# WiFiChessSch.net
KiCad netlist of a schematic drawn in Altium Designer
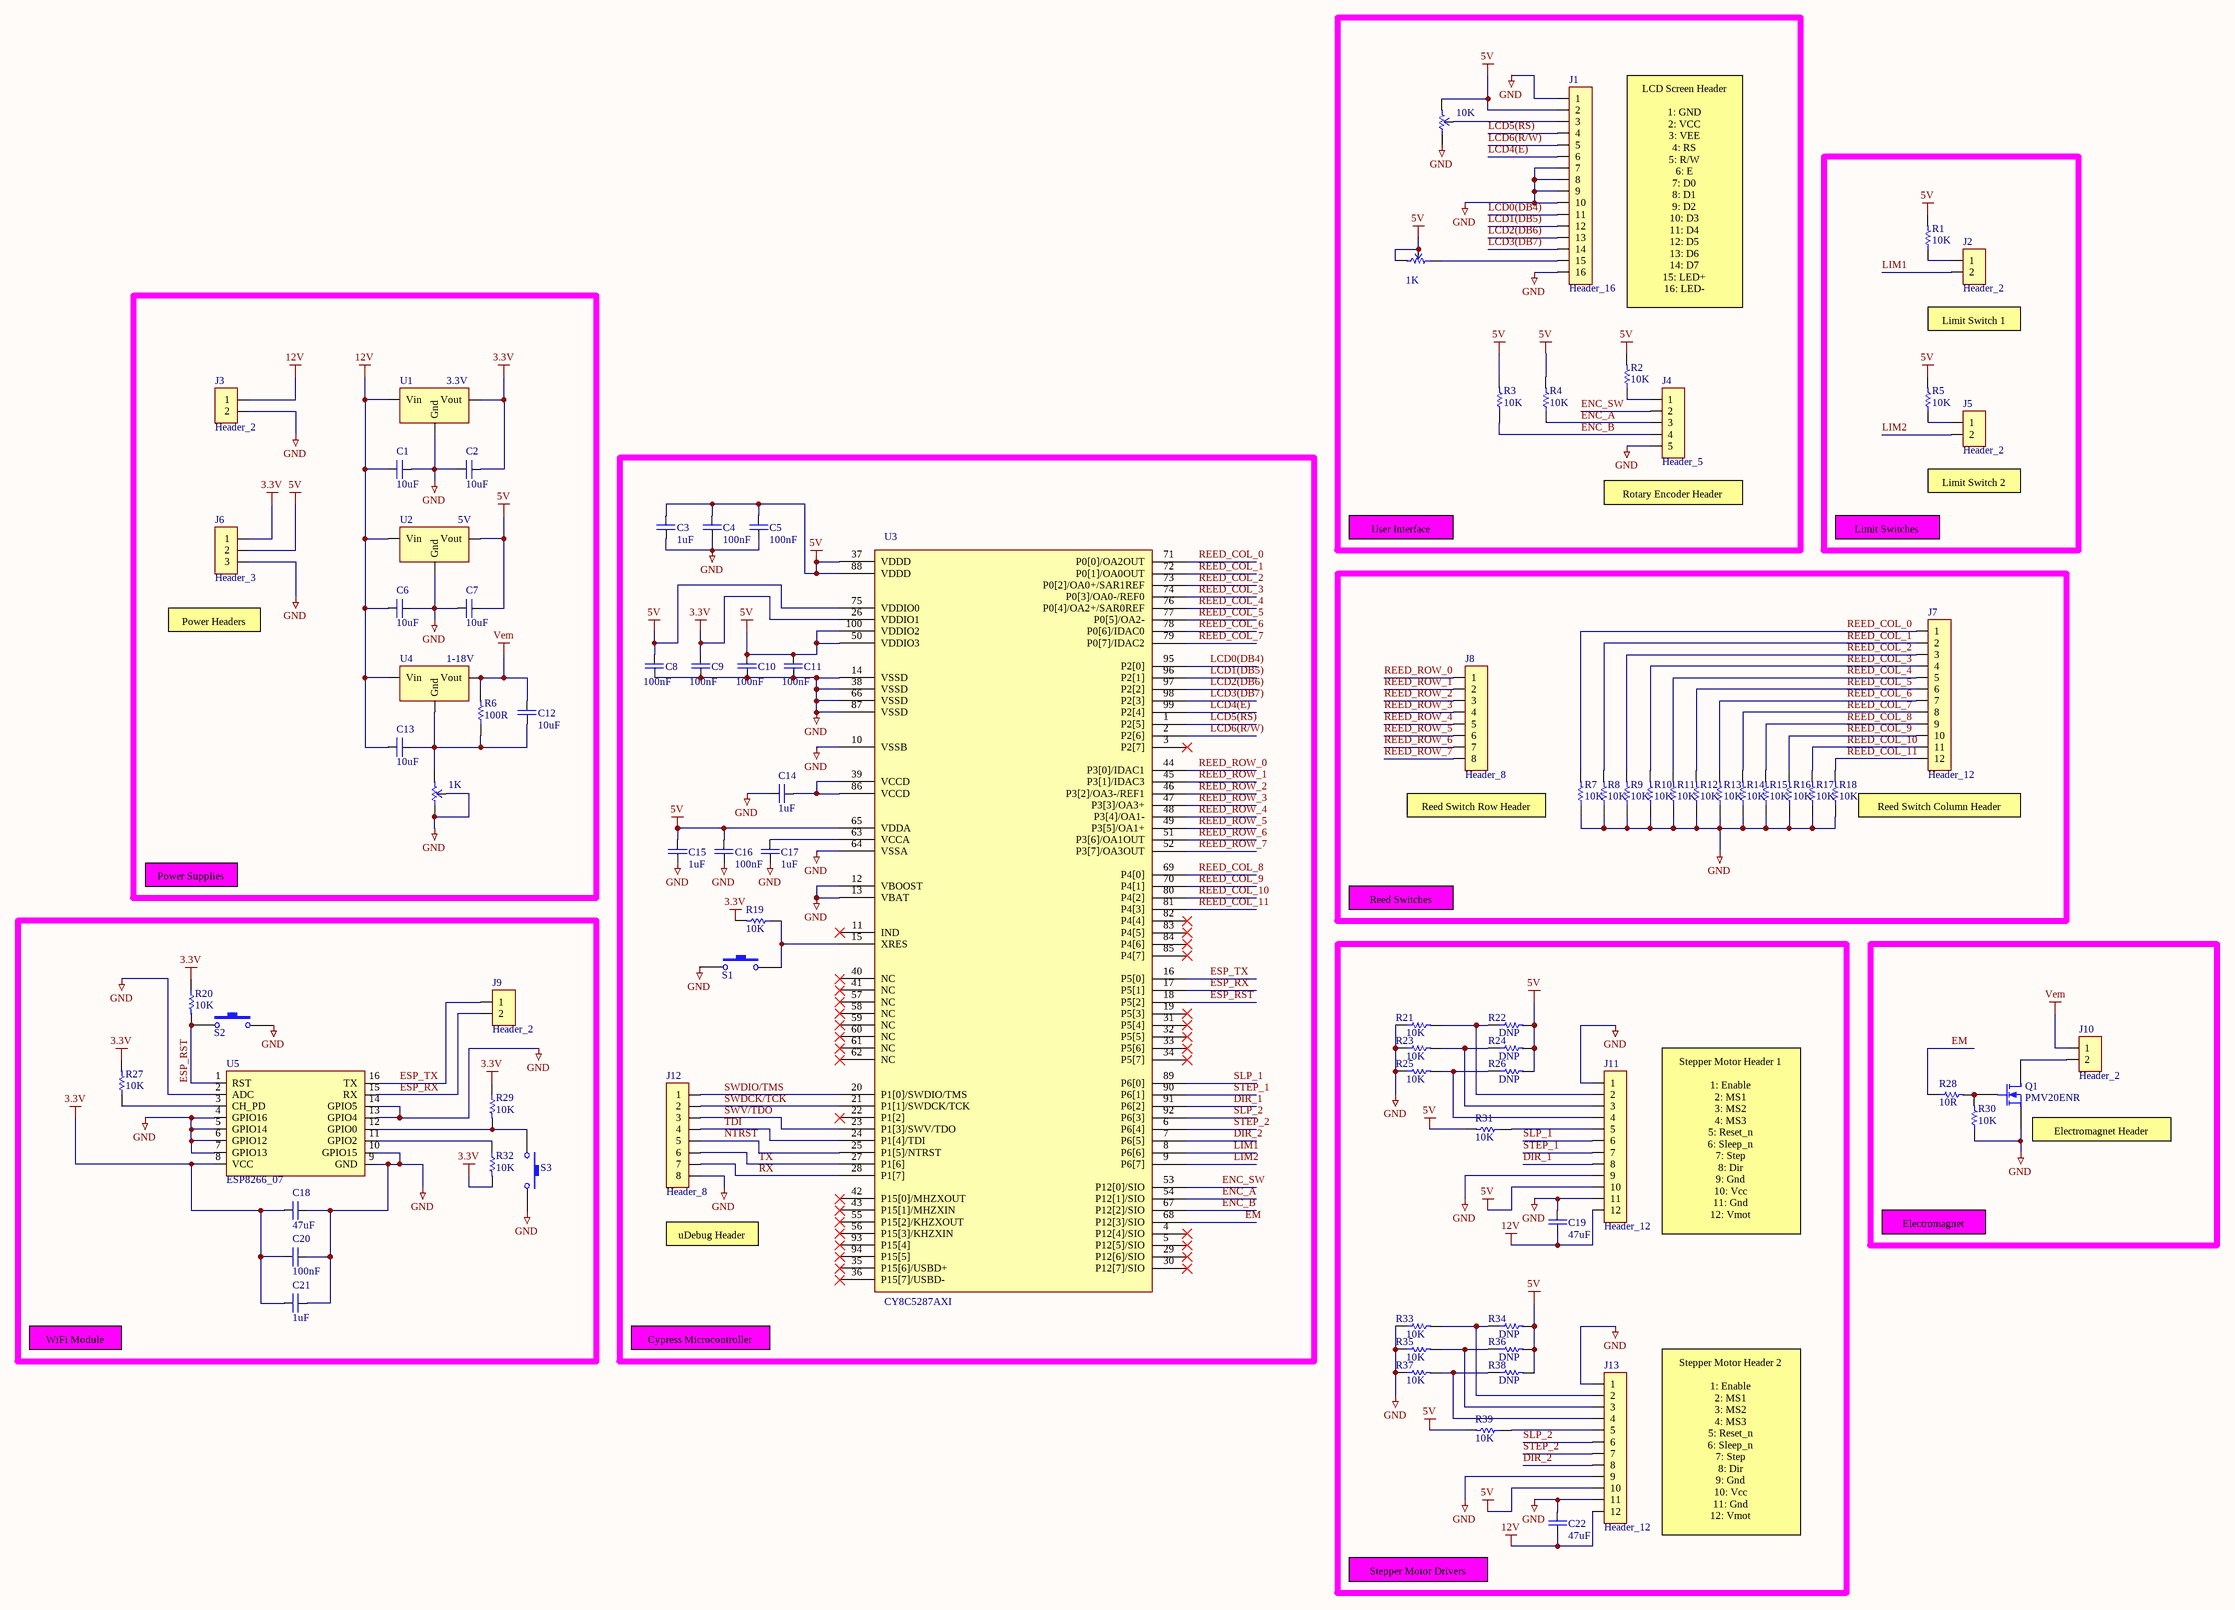
[diagram p0: WiFiChessSch.SchDoc]

(export (version "E")
  (design (tool "Eeschema 10.0.6"))
  (components
    (comp (ref "C1")
      (value "10uF")
      (footprint "CAP0603")
      (libsource (lib "Capacitor_0603") (part "Cap_10uF_0603"))
    )
    (comp (ref "C2")
      (value "10uF")
      (footprint "CAP0603")
      (libsource (lib "Capacitor_0603") (part "Cap_10uF_0603"))
    )
    (comp (ref "C3")
      (value "1uF")
      (footprint "CAP0603")
      (libsource (lib "Capacitor_0603") (part "Cap_1uF_0603"))
    )
    (comp (ref "C4")
      (value "100nF")
      (footprint "CAP0603")
      (libsource (lib "Capacitor_0603") (part "Cap_100nF_0603"))
    )
    (comp (ref "C5")
      (value "100nF")
      (footprint "CAP0603")
      (libsource (lib "Capacitor_0603") (part "Cap_100nF_0603"))
    )
    (comp (ref "C6")
      (value "10uF")
      (footprint "CAP0603")
      (libsource (lib "Capacitor_0603") (part "Cap_10uF_0603"))
    )
    (comp (ref "C7")
      (value "10uF")
      (footprint "CAP0603")
      (libsource (lib "Capacitor_0603") (part "Cap_10uF_0603"))
    )
    (comp (ref "C8")
      (value "100nF")
      (footprint "CAP0603")
      (libsource (lib "Capacitor_0603") (part "Cap_100nF_0603"))
    )
    (comp (ref "C9")
      (value "100nF")
      (footprint "CAP0603")
      (libsource (lib "Capacitor_0603") (part "Cap_100nF_0603"))
    )
    (comp (ref "C10")
      (value "100nF")
      (footprint "CAP0603")
      (libsource (lib "Capacitor_0603") (part "Cap_100nF_0603"))
    )
    (comp (ref "C11")
      (value "100nF")
      (footprint "CAP0603")
      (libsource (lib "Capacitor_0603") (part "Cap_100nF_0603"))
    )
    (comp (ref "C12")
      (value "10uF")
      (footprint "CAP0603")
      (libsource (lib "Capacitor_0603") (part "Cap_10uF_0603"))
    )
    (comp (ref "C13")
      (value "10uF")
      (footprint "CAP0603")
      (libsource (lib "Capacitor_0603") (part "Cap_10uF_0603"))
    )
    (comp (ref "C14")
      (value "1uF")
      (footprint "CAP0603")
      (libsource (lib "Capacitor_0603") (part "Cap_1uF_0603"))
    )
    (comp (ref "C15")
      (value "1uF")
      (footprint "CAP0603")
      (libsource (lib "Capacitor_0603") (part "Cap_1uF_0603"))
    )
    (comp (ref "C16")
      (value "100nF")
      (footprint "CAP0603")
      (libsource (lib "Capacitor_0603") (part "Cap_100nF_0603"))
    )
    (comp (ref "C17")
      (value "1uF")
      (footprint "CAP0603")
      (libsource (lib "Capacitor_0603") (part "Cap_1uF_0603"))
    )
    (comp (ref "C18")
      (value "47uF")
      (footprint "CAP_EL_8x5.9")
      (fields (field (name "MANUFACTURER") "Nichicon") (field (name "PART NUMBER") "UWT1E470MCL6GS"))
      (libsource (lib "Capacitor_Aluminum") (part "Cap_47uF_Alu"))
    )
    (comp (ref "C19")
      (value "47uF")
      (footprint "CAP_EL_8x5.9")
      (fields (field (name "MANUFACTURER") "Nichicon") (field (name "PART NUMBER") "UWT1E470MCL6GS"))
      (libsource (lib "Capacitor_Aluminum") (part "Cap_47uF_Alu"))
    )
    (comp (ref "C20")
      (value "100nF")
      (footprint "CAP0603")
      (libsource (lib "Capacitor_0603") (part "Cap_100nF_0603"))
    )
    (comp (ref "C21")
      (value "1uF")
      (footprint "CAP0603")
      (libsource (lib "Capacitor_0603") (part "Cap_1uF_0603"))
    )
    (comp (ref "C22")
      (value "47uF")
      (footprint "CAP_EL_8x5.9")
      (fields (field (name "MANUFACTURER") "Nichicon") (field (name "PART NUMBER") "UWT1E470MCL6GS"))
      (libsource (lib "Capacitor_Aluminum") (part "Cap_47uF_Alu"))
    )
    (comp (ref "J1")
      (value "Header_16")
      (footprint "16 Pin Header 2.54mm")
      (description "16 pin header")
      (libsource (lib "Connectors") (part "Header_16"))
    )
    (comp (ref "J2")
      (value "Header_2")
      (footprint "2 Pin Header 2.54mm")
      (description "2 Pin Header")
      (libsource (lib "Connectors") (part "Header_2"))
    )
    (comp (ref "J3")
      (value "Header_2")
      (footprint "2 Pin Header 2.54mm")
      (description "2 Pin Header")
      (libsource (lib "") (part "Header_2_1"))
    )
    (comp (ref "J4")
      (value "Header_5")
      (footprint "5 Pin Header 2.54mm")
      (description "5 Pin Header")
      (libsource (lib "Connectors") (part "Header_5"))
    )
    (comp (ref "J5")
      (value "Header_2")
      (footprint "2 Pin Header 2.54mm")
      (description "2 Pin Header")
      (libsource (lib "Connectors") (part "Header_2"))
    )
    (comp (ref "J6")
      (value "Header_3")
      (footprint "3 Pin Header 2.54mm")
      (description "3 Pin Header")
      (libsource (lib "Connectors") (part "Header_3"))
    )
    (comp (ref "J7")
      (value "Header_12")
      (footprint "12 Pin Header 2.54mm")
      (description "12 Pin Header")
      (libsource (lib "Connectors") (part "Header_12"))
    )
    (comp (ref "J8")
      (value "Header_8")
      (footprint "8 Pin Header 2.54mm")
      (description "8 Pin Header")
      (libsource (lib "") (part "Header_8_1"))
    )
    (comp (ref "J9")
      (value "Header_2")
      (footprint "2 Pin Header 2.54mm")
      (description "2 Pin Header")
      (libsource (lib "Connectors") (part "Header_2"))
    )
    (comp (ref "J10")
      (value "Header_2")
      (footprint "2 Pin Header 2.54mm")
      (description "2 Pin Header")
      (libsource (lib "Connectors") (part "Header_2"))
    )
    (comp (ref "J11")
      (value "Header_12")
      (footprint "12 Pin Header 2.54mm")
      (description "12 Pin Header")
      (libsource (lib "Connectors") (part "Header_12"))
    )
    (comp (ref "J12")
      (value "Header_8")
      (footprint "8 Pin Header 2.54mm")
      (description "8 Pin Header")
      (libsource (lib "Connectors") (part "Header_8"))
    )
    (comp (ref "J13")
      (value "Header_12")
      (footprint "12 Pin Header 2.54mm")
      (description "12 Pin Header")
      (libsource (lib "Connectors") (part "Header_12"))
    )
    (comp (ref "Q1")
      (value "PMV20ENR")
      (footprint "SOT23")
      (description "Logic Level P-FET")
      (fields (field (name "MANUFACTURER") "NXP Semiconductor"))
      (libsource (lib "Transistors") (part "PMV20ENR"))
    )
    (comp (ref "R1")
      (value "10K")
      (footprint "RES0603")
      (description "Resistor")
      (fields (field (name "PART NUMBER") "RC0603JR-0710KL") (field (name "MANUFACTURER") "Yageo"))
      (libsource (lib "Resistor_0603") (part "Res_10K_0603"))
    )
    (comp (ref "R2")
      (value "10K")
      (footprint "RES0603")
      (description "Resistor")
      (fields (field (name "PART NUMBER") "RC0603JR-0710KL") (field (name "MANUFACTURER") "Yageo"))
      (libsource (lib "Resistor_0603") (part "Res_10K_0603"))
    )
    (comp (ref "R3")
      (value "10K")
      (footprint "RES0603")
      (description "Resistor")
      (fields (field (name "PART NUMBER") "RC0603JR-0710KL") (field (name "MANUFACTURER") "Yageo"))
      (libsource (lib "Resistor_0603") (part "Res_10K_0603"))
    )
    (comp (ref "R4")
      (value "10K")
      (footprint "RES0603")
      (description "Resistor")
      (fields (field (name "PART NUMBER") "RC0603JR-0710KL") (field (name "MANUFACTURER") "Yageo"))
      (libsource (lib "Resistor_0603") (part "Res_10K_0603"))
    )
    (comp (ref "R5")
      (value "10K")
      (footprint "RES0603")
      (description "Resistor")
      (fields (field (name "PART NUMBER") "RC0603JR-0710KL") (field (name "MANUFACTURER") "Yageo"))
      (libsource (lib "Resistor_0603") (part "Res_10K_0603"))
    )
    (comp (ref "R6")
      (value "100R")
      (footprint "RES0603")
      (description "Resistor")
      (fields (field (name "TOLERANCE") "5%"))
      (libsource (lib "Resistor_0603") (part "Res_100R_0603_1"))
    )
    (comp (ref "R7")
      (value "10K")
      (footprint "RES0603")
      (description "Resistor")
      (fields (field (name "PART NUMBER") "RC0603JR-0710KL") (field (name "MANUFACTURER") "Yageo"))
      (libsource (lib "Resistor_0603") (part "Res_10K_0603"))
    )
    (comp (ref "R8")
      (value "10K")
      (footprint "RES0603")
      (description "Resistor")
      (fields (field (name "PART NUMBER") "RC0603JR-0710KL") (field (name "MANUFACTURER") "Yageo"))
      (libsource (lib "Resistor_0603") (part "Res_10K_0603"))
    )
    (comp (ref "R9")
      (value "10K")
      (footprint "RES0603")
      (description "Resistor")
      (fields (field (name "PART NUMBER") "RC0603JR-0710KL") (field (name "MANUFACTURER") "Yageo"))
      (libsource (lib "Resistor_0603") (part "Res_10K_0603"))
    )
    (comp (ref "R10")
      (value "10K")
      (footprint "RES0603")
      (description "Resistor")
      (fields (field (name "PART NUMBER") "RC0603JR-0710KL") (field (name "MANUFACTURER") "Yageo"))
      (libsource (lib "Resistor_0603") (part "Res_10K_0603"))
    )
    (comp (ref "R11")
      (value "10K")
      (footprint "RES0603")
      (description "Resistor")
      (fields (field (name "PART NUMBER") "RC0603JR-0710KL") (field (name "MANUFACTURER") "Yageo"))
      (libsource (lib "Resistor_0603") (part "Res_10K_0603"))
    )
    (comp (ref "R12")
      (value "10K")
      (footprint "RES0603")
      (description "Resistor")
      (fields (field (name "PART NUMBER") "RC0603JR-0710KL") (field (name "MANUFACTURER") "Yageo"))
      (libsource (lib "Resistor_0603") (part "Res_10K_0603"))
    )
    (comp (ref "R13")
      (value "10K")
      (footprint "RES0603")
      (description "Resistor")
      (fields (field (name "PART NUMBER") "RC0603JR-0710KL") (field (name "MANUFACTURER") "Yageo"))
      (libsource (lib "Resistor_0603") (part "Res_10K_0603"))
    )
    (comp (ref "R14")
      (value "10K")
      (footprint "RES0603")
      (description "Resistor")
      (fields (field (name "PART NUMBER") "RC0603JR-0710KL") (field (name "MANUFACTURER") "Yageo"))
      (libsource (lib "Resistor_0603") (part "Res_10K_0603"))
    )
    (comp (ref "R15")
      (value "10K")
      (footprint "RES0603")
      (description "Resistor")
      (fields (field (name "PART NUMBER") "RC0603JR-0710KL") (field (name "MANUFACTURER") "Yageo"))
      (libsource (lib "Resistor_0603") (part "Res_10K_0603"))
    )
    (comp (ref "R16")
      (value "10K")
      (footprint "RES0603")
      (description "Resistor")
      (fields (field (name "PART NUMBER") "RC0603JR-0710KL") (field (name "MANUFACTURER") "Yageo"))
      (libsource (lib "Resistor_0603") (part "Res_10K_0603"))
    )
    (comp (ref "R17")
      (value "10K")
      (footprint "RES0603")
      (description "Resistor")
      (fields (field (name "PART NUMBER") "RC0603JR-0710KL") (field (name "MANUFACTURER") "Yageo"))
      (libsource (lib "Resistor_0603") (part "Res_10K_0603"))
    )
    (comp (ref "R18")
      (value "10K")
      (footprint "RES0603")
      (description "Resistor")
      (fields (field (name "PART NUMBER") "RC0603JR-0710KL") (field (name "MANUFACTURER") "Yageo"))
      (libsource (lib "Resistor_0603") (part "Res_10K_0603"))
    )
    (comp (ref "R19")
      (value "10K")
      (footprint "RES0603")
      (description "Resistor")
      (fields (field (name "PART NUMBER") "RC0603JR-0710KL") (field (name "MANUFACTURER") "Yageo"))
      (libsource (lib "Resistor_0603") (part "Res_10K_0603"))
    )
    (comp (ref "R20")
      (value "10K")
      (footprint "RES0603")
      (description "Resistor")
      (fields (field (name "PART NUMBER") "RC0603JR-0710KL") (field (name "MANUFACTURER") "Yageo"))
      (libsource (lib "Resistor_0603") (part "Res_10K_0603"))
    )
    (comp (ref "R21")
      (value "10K")
      (footprint "RES0603")
      (description "Resistor")
      (fields (field (name "PART NUMBER") "RC0603JR-0710KL") (field (name "MANUFACTURER") "Yageo"))
      (libsource (lib "Resistor_0603") (part "Res_10K_0603"))
    )
    (comp (ref "R22")
      (value "DNP")
      (footprint "RES0603")
      (description "Resistor")
      (fields (field (name "TOLERANCE") "5%"))
      (libsource (lib "Resistor_0603") (part "Res_0603_DNP"))
    )
    (comp (ref "R23")
      (value "10K")
      (footprint "RES0603")
      (description "Resistor")
      (fields (field (name "PART NUMBER") "RC0603JR-0710KL") (field (name "MANUFACTURER") "Yageo"))
      (libsource (lib "Resistor_0603") (part "Res_10K_0603"))
    )
    (comp (ref "R24")
      (value "DNP")
      (footprint "RES0603")
      (description "Resistor")
      (fields (field (name "TOLERANCE") "5%"))
      (libsource (lib "Resistor_0603") (part "Res_0603_DNP"))
    )
    (comp (ref "R25")
      (value "10K")
      (footprint "RES0603")
      (description "Resistor")
      (fields (field (name "PART NUMBER") "RC0603JR-0710KL") (field (name "MANUFACTURER") "Yageo"))
      (libsource (lib "Resistor_0603") (part "Res_10K_0603"))
    )
    (comp (ref "R26")
      (value "DNP")
      (footprint "RES0603")
      (description "Resistor")
      (fields (field (name "TOLERANCE") "5%"))
      (libsource (lib "Resistor_0603") (part "Res_0603_DNP"))
    )
    (comp (ref "R27")
      (value "10K")
      (footprint "RES0603")
      (description "Resistor")
      (fields (field (name "PART NUMBER") "RC0603JR-0710KL") (field (name "MANUFACTURER") "Yageo"))
      (libsource (lib "Resistor_0603") (part "Res_10K_0603"))
    )
    (comp (ref "R28")
      (value "10R")
      (footprint "RES0603")
      (description "Resistor")
      (fields (field (name "TOLERANCE") "5%"))
      (libsource (lib "Resistor_0603") (part "Res_10R_0603"))
    )
    (comp (ref "R29")
      (value "10K")
      (footprint "RES0603")
      (description "Resistor")
      (fields (field (name "PART NUMBER") "RC0603JR-0710KL") (field (name "MANUFACTURER") "Yageo"))
      (libsource (lib "Resistor_0603") (part "Res_10K_0603"))
    )
    (comp (ref "R30")
      (value "10K")
      (footprint "RES0603")
      (description "Resistor")
      (fields (field (name "PART NUMBER") "RC0603JR-0710KL") (field (name "MANUFACTURER") "Yageo"))
      (libsource (lib "Resistor_0603") (part "Res_10K_0603"))
    )
    (comp (ref "R31")
      (value "10K")
      (footprint "RES0603")
      (description "Resistor")
      (fields (field (name "PART NUMBER") "RC0603JR-0710KL") (field (name "MANUFACTURER") "Yageo"))
      (libsource (lib "Resistor_0603") (part "Res_10K_0603"))
    )
    (comp (ref "R32")
      (value "10K")
      (footprint "RES0603")
      (description "Resistor")
      (fields (field (name "PART NUMBER") "RC0603JR-0710KL") (field (name "MANUFACTURER") "Yageo"))
      (libsource (lib "Resistor_0603") (part "Res_10K_0603"))
    )
    (comp (ref "R33")
      (value "10K")
      (footprint "RES0603")
      (description "Resistor")
      (fields (field (name "PART NUMBER") "RC0603JR-0710KL") (field (name "MANUFACTURER") "Yageo"))
      (libsource (lib "Resistor_0603") (part "Res_10K_0603"))
    )
    (comp (ref "R34")
      (value "DNP")
      (footprint "RES0603")
      (description "Resistor")
      (fields (field (name "TOLERANCE") "5%"))
      (libsource (lib "Resistor_0603") (part "Res_0603_DNP"))
    )
    (comp (ref "R35")
      (value "10K")
      (footprint "RES0603")
      (description "Resistor")
      (fields (field (name "PART NUMBER") "RC0603JR-0710KL") (field (name "MANUFACTURER") "Yageo"))
      (libsource (lib "Resistor_0603") (part "Res_10K_0603"))
    )
    (comp (ref "R36")
      (value "DNP")
      (footprint "RES0603")
      (description "Resistor")
      (fields (field (name "TOLERANCE") "5%"))
      (libsource (lib "Resistor_0603") (part "Res_0603_DNP"))
    )
    (comp (ref "R37")
      (value "10K")
      (footprint "RES0603")
      (description "Resistor")
      (fields (field (name "PART NUMBER") "RC0603JR-0710KL") (field (name "MANUFACTURER") "Yageo"))
      (libsource (lib "Resistor_0603") (part "Res_10K_0603"))
    )
    (comp (ref "R38")
      (value "DNP")
      (footprint "RES0603")
      (description "Resistor")
      (fields (field (name "TOLERANCE") "5%"))
      (libsource (lib "Resistor_0603") (part "Res_0603_DNP"))
    )
    (comp (ref "R39")
      (value "10K")
      (footprint "RES0603")
      (description "Resistor")
      (fields (field (name "PART NUMBER") "RC0603JR-0710KL") (field (name "MANUFACTURER") "Yageo"))
      (libsource (lib "Resistor_0603") (part "Res_10K_0603"))
    )
    (comp (ref "S1")
      (value "NO-Tactile Switch")
      (footprint "FSM2JSMAATR")
      (description "Switch")
      (fields
        (field (name "PART NUMBER") "PTS645SK50SMTR92 LFS")
        (field (name "MANUFACTURER") "C&K Components")
      )
      (libsource (lib "Switches") (part "NO-Tactile Switch"))
    )
    (comp (ref "S2")
      (value "NO-Tactile Switch")
      (footprint "FSM2JSMAATR")
      (description "Switch")
      (fields
        (field (name "PART NUMBER") "PTS645SK50SMTR92 LFS")
        (field (name "MANUFACTURER") "C&K Components")
      )
      (libsource (lib "Switches") (part "NO-Tactile Switch"))
    )
    (comp (ref "S3")
      (value "NO-Tactile Switch")
      (footprint "FSM2JSMAATR")
      (description "Switch")
      (fields
        (field (name "PART NUMBER") "PTS645SK50SMTR92 LFS")
        (field (name "MANUFACTURER") "C&K Components")
      )
      (libsource (lib "Switches") (part "NO-Tactile Switch"))
    )
    (comp (ref "U1")
      (value "3.3V")
      (footprint "SOT223")
      (description "3.3V_800mA_Linear")
      (fields (field (name "PART NUMBER") "NCP1117ST33T3G") (field (name "MANUFACTURER") "ON Semiconductor"))
      (libsource (lib "Voltage_Regulators") (part "NCP1117ST33T3G"))
    )
    (comp (ref "U2")
      (value "5V")
      (footprint "SOT223")
      (description "5V_1A_Linear")
      (fields (field (name "PART NUMBER") "NCV1117ST50T3G") (field (name "MANUFACTURER") "ON Semiconductor"))
      (libsource (lib "Voltage_Regulators") (part "NCV1117ST50T3G"))
    )
    (comp (ref "U3")
      (value "CY8C5287AXI")
      (footprint "TQPF-100")
      (description "Cypress CY8C52 PSoC 5")
      (fields
        (field (name "PART NUMBER") "CY8C5287AXI-LP095")
        (field (name "MANUFACTURER") "Cypress Semiconductor")
      )
      (libsource (lib "Microcontrollers") (part "CY8C5287AXI"))
    )
    (comp (ref "U4")
      (value "1-18V")
      (footprint "SOT223")
      (description "Adj_1A_Linear")
      (fields (field (name "PART NUMBER") "NCV1117STAT3G") (field (name "MANUFACTURER") "ON Semiconductor"))
      (libsource (lib "Voltage_Regulators") (part "NCV1117STAT3G"))
    )
    (comp (ref "U5")
      (value "ESP8266_07")
      (footprint "ESP-07")
      (description "ESP-07 WiFi Module")
      (libsource (lib "Modules") (part "ESP8266_07"))
    )
    (comp (ref "VR1")
      (value "10K")
      (footprint "RESPVZ3A")
      (fields
        (field (name "PART NUMBER") "PVZ3A103C01R00")
        (field (name "MANUFACTURER") "Murata Electronics")
      )
      (libsource (lib "Potentiometer") (part "PVZ3A_10K_Trimmer_Pot"))
    )
    (comp (ref "VR2")
      (value "1K")
      (footprint "RESPVZ3A")
      (fields
        (field (name "PART NUMBER") "PVZ3A102C01R00")
        (field (name "MANUFACTURER") "Murata Electronics")
      )
      (libsource (lib "Potentiometer") (part "PVZ3A_1K_Trimmer_Pot"))
    )
    (comp (ref "VR3")
      (value "1K")
      (footprint "RESPVZ3A")
      (fields
        (field (name "PART NUMBER") "PVZ3A102C01R00")
        (field (name "MANUFACTURER") "Murata Electronics")
      )
      (libsource (lib "Potentiometer") (part "PVZ3A_1K_Trimmer_Pot"))
    )
  )
  (nets
    (net (code "1") (name "/DIR_1") (class "Default")
      (node (ref "J11") (pin "8") (pinfunction "8_8") (pintype "passive"))
      (node (ref "U3") (pin "91") (pinfunction "P6[2]_91") (pintype "passive"))
    )
    (net (code "2") (name "/DIR_2") (class "Default")
      (node (ref "J13") (pin "8") (pinfunction "8_8") (pintype "passive"))
      (node (ref "U3") (pin "7") (pinfunction "P6[5]_7") (pintype "passive"))
    )
    (net (code "3") (name "/EM") (class "Default")
      (node (ref "R28") (pin "1") (pinfunction "1_1") (pintype "passive"))
      (node (ref "U3") (pin "68") (pinfunction "P12[3]/SIO_68") (pintype "passive"))
    )
    (net (code "4") (name "/ENC_A") (class "Default")
      (node (ref "J4") (pin "3") (pinfunction "3_3") (pintype "passive"))
      (node (ref "R4") (pin "1") (pinfunction "1_1") (pintype "passive"))
      (node (ref "U3") (pin "54") (pinfunction "P12[1]/SIO_54") (pintype "passive"))
    )
    (net (code "5") (name "/ENC_B") (class "Default")
      (node (ref "J4") (pin "4") (pinfunction "4_4") (pintype "passive"))
      (node (ref "R3") (pin "1") (pinfunction "1_1") (pintype "passive"))
      (node (ref "U3") (pin "67") (pinfunction "P12[2]/SIO_67") (pintype "passive"))
    )
    (net (code "6") (name "/ENC_SW") (class "Default")
      (node (ref "J4") (pin "2") (pinfunction "2_2") (pintype "passive"))
      (node (ref "U3") (pin "53") (pinfunction "P12[0]/SIO_53") (pintype "passive"))
    )
    (net (code "7") (name "/ESP_RST") (class "Default")
      (node (ref "R20") (pin "2") (pinfunction "2_2") (pintype "passive"))
      (node (ref "S2") (pin "1") (pinfunction "1_1") (pintype "passive"))
      (node (ref "U3") (pin "18") (pinfunction "P5[2]_18") (pintype "passive"))
      (node (ref "U5") (pin "1") (pinfunction "RST_1") (pintype "passive"))
    )
    (net (code "8") (name "/ESP_RX") (class "Default")
      (node (ref "J9") (pin "2") (pinfunction "2_2") (pintype "passive"))
      (node (ref "U3") (pin "17") (pinfunction "P5[1]_17") (pintype "passive"))
      (node (ref "U5") (pin "15") (pinfunction "RX_15") (pintype "passive"))
    )
    (net (code "9") (name "/ESP_TX") (class "Default")
      (node (ref "J9") (pin "1") (pinfunction "1_1") (pintype "passive"))
      (node (ref "U3") (pin "16") (pinfunction "P5[0]_16") (pintype "passive"))
      (node (ref "U5") (pin "16") (pinfunction "TX_16") (pintype "passive"))
    )
    (net (code "10") (name "/LCD0(DB4)") (class "Default")
      (node (ref "J1") (pin "11") (pinfunction "11_11") (pintype "passive"))
      (node (ref "U3") (pin "95") (pinfunction "P2[0]_95") (pintype "passive"))
    )
    (net (code "11") (name "/LCD1(DB5)") (class "Default")
      (node (ref "J1") (pin "12") (pinfunction "12_12") (pintype "passive"))
      (node (ref "U3") (pin "96") (pinfunction "P2[1]_96") (pintype "passive"))
    )
    (net (code "12") (name "/LCD2(DB6)") (class "Default")
      (node (ref "J1") (pin "13") (pinfunction "13_13") (pintype "passive"))
      (node (ref "U3") (pin "97") (pinfunction "P2[2]_97") (pintype "passive"))
    )
    (net (code "13") (name "/LCD3(DB7)") (class "Default")
      (node (ref "J1") (pin "14") (pinfunction "14_14") (pintype "passive"))
      (node (ref "U3") (pin "98") (pinfunction "P2[3]_98") (pintype "passive"))
    )
    (net (code "14") (name "/LCD4(E)") (class "Default")
      (node (ref "J1") (pin "6") (pinfunction "6_6") (pintype "passive"))
      (node (ref "U3") (pin "99") (pinfunction "P2[4]_99") (pintype "passive"))
    )
    (net (code "15") (name "/LCD5(RS)") (class "Default")
      (node (ref "J1") (pin "4") (pinfunction "4_4") (pintype "passive"))
      (node (ref "U3") (pin "1") (pinfunction "P2[5]_1") (pintype "passive"))
    )
    (net (code "16") (name "/LCD6(R{slash}W)") (class "Default")
      (node (ref "J1") (pin "5") (pinfunction "5_5") (pintype "passive"))
      (node (ref "U3") (pin "2") (pinfunction "P2[6]_2") (pintype "passive"))
    )
    (net (code "17") (name "/LIM1") (class "Default")
      (node (ref "J2") (pin "2") (pinfunction "2_2") (pintype "passive"))
      (node (ref "U3") (pin "8") (pinfunction "P6[6]_8") (pintype "passive"))
    )
    (net (code "18") (name "/LIM2") (class "Default")
      (node (ref "J5") (pin "2") (pinfunction "2_2") (pintype "passive"))
      (node (ref "U3") (pin "9") (pinfunction "P6[7]_9") (pintype "passive"))
    )
    (net (code "19") (name "/NTRST") (class "Default")
      (node (ref "J12") (pin "5") (pinfunction "5_5") (pintype "passive"))
      (node (ref "U3") (pin "25") (pinfunction "P1[5]/NTRST_25") (pintype "passive"))
    )
    (net (code "20") (name "/REED_COL_0") (class "Default")
      (node (ref "J7") (pin "1") (pinfunction "1_1") (pintype "passive"))
      (node (ref "R7") (pin "2") (pinfunction "2_2") (pintype "passive"))
      (node (ref "U3") (pin "71") (pinfunction "P0[0]/OA2OUT_71") (pintype "passive"))
    )
    (net (code "21") (name "/REED_COL_1") (class "Default")
      (node (ref "J7") (pin "2") (pinfunction "2_2") (pintype "passive"))
      (node (ref "R8") (pin "2") (pinfunction "2_2") (pintype "passive"))
      (node (ref "U3") (pin "72") (pinfunction "P0[1]/OA0OUT_72") (pintype "passive"))
    )
    (net (code "22") (name "/REED_COL_2") (class "Default")
      (node (ref "J7") (pin "3") (pinfunction "3_3") (pintype "passive"))
      (node (ref "R9") (pin "2") (pinfunction "2_2") (pintype "passive"))
      (node (ref "U3") (pin "73") (pinfunction "P0[2]/OA0+/SAR1REF_73") (pintype "passive"))
    )
    (net (code "23") (name "/REED_COL_3") (class "Default")
      (node (ref "J7") (pin "4") (pinfunction "4_4") (pintype "passive"))
      (node (ref "R10") (pin "2") (pinfunction "2_2") (pintype "passive"))
      (node (ref "U3") (pin "74") (pinfunction "P0[3]/OA0-/REF0_74") (pintype "passive"))
    )
    (net (code "24") (name "/REED_COL_4") (class "Default")
      (node (ref "J7") (pin "5") (pinfunction "5_5") (pintype "passive"))
      (node (ref "R11") (pin "2") (pinfunction "2_2") (pintype "passive"))
      (node (ref "U3") (pin "76") (pinfunction "P0[4]/OA2+/SAR0REF_76") (pintype "passive"))
    )
    (net (code "25") (name "/REED_COL_5") (class "Default")
      (node (ref "J7") (pin "6") (pinfunction "6_6") (pintype "passive"))
      (node (ref "R12") (pin "2") (pinfunction "2_2") (pintype "passive"))
      (node (ref "U3") (pin "77") (pinfunction "P0[5]/OA2-_77") (pintype "passive"))
    )
    (net (code "26") (name "/REED_COL_6") (class "Default")
      (node (ref "J7") (pin "7") (pinfunction "7_7") (pintype "passive"))
      (node (ref "R13") (pin "2") (pinfunction "2_2") (pintype "passive"))
      (node (ref "U3") (pin "78") (pinfunction "P0[6]/IDAC0_78") (pintype "passive"))
    )
    (net (code "27") (name "/REED_COL_7") (class "Default")
      (node (ref "J7") (pin "8") (pinfunction "8_8") (pintype "passive"))
      (node (ref "R14") (pin "2") (pinfunction "2_2") (pintype "passive"))
      (node (ref "U3") (pin "79") (pinfunction "P0[7]/IDAC2_79") (pintype "passive"))
    )
    (net (code "28") (name "/REED_COL_8") (class "Default")
      (node (ref "J7") (pin "9") (pinfunction "9_9") (pintype "passive"))
      (node (ref "R15") (pin "2") (pinfunction "2_2") (pintype "passive"))
      (node (ref "U3") (pin "69") (pinfunction "P4[0]_69") (pintype "passive"))
    )
    (net (code "29") (name "/REED_COL_9") (class "Default")
      (node (ref "J7") (pin "10") (pinfunction "10_10") (pintype "passive"))
      (node (ref "R16") (pin "2") (pinfunction "2_2") (pintype "passive"))
      (node (ref "U3") (pin "70") (pinfunction "P4[1]_70") (pintype "passive"))
    )
    (net (code "30") (name "/REED_COL_10") (class "Default")
      (node (ref "J7") (pin "11") (pinfunction "11_11") (pintype "passive"))
      (node (ref "R17") (pin "2") (pinfunction "2_2") (pintype "passive"))
      (node (ref "U3") (pin "80") (pinfunction "P4[2]_80") (pintype "passive"))
    )
    (net (code "31") (name "/REED_COL_11") (class "Default")
      (node (ref "J7") (pin "12") (pinfunction "12_12") (pintype "passive"))
      (node (ref "R18") (pin "2") (pinfunction "2_2") (pintype "passive"))
      (node (ref "U3") (pin "81") (pinfunction "P4[3]_81") (pintype "passive"))
    )
    (net (code "32") (name "/REED_ROW_0") (class "Default")
      (node (ref "J8") (pin "1") (pinfunction "1_1") (pintype "passive"))
      (node (ref "U3") (pin "44") (pinfunction "P3[0]/IDAC1_44") (pintype "passive"))
    )
    (net (code "33") (name "/REED_ROW_1") (class "Default")
      (node (ref "J8") (pin "2") (pinfunction "2_2") (pintype "passive"))
      (node (ref "U3") (pin "45") (pinfunction "P3[1]/IDAC3_45") (pintype "passive"))
    )
    (net (code "34") (name "/REED_ROW_2") (class "Default")
      (node (ref "J8") (pin "3") (pinfunction "3_3") (pintype "passive"))
      (node (ref "U3") (pin "46") (pinfunction "P3[2]/OA3-/REF1_46") (pintype "passive"))
    )
    (net (code "35") (name "/REED_ROW_3") (class "Default")
      (node (ref "J8") (pin "4") (pinfunction "4_4") (pintype "passive"))
      (node (ref "U3") (pin "47") (pinfunction "P3[3]/OA3+_47") (pintype "passive"))
    )
    (net (code "36") (name "/REED_ROW_4") (class "Default")
      (node (ref "J8") (pin "5") (pinfunction "5_5") (pintype "passive"))
      (node (ref "U3") (pin "48") (pinfunction "P3[4]/OA1-_48") (pintype "passive"))
    )
    (net (code "37") (name "/REED_ROW_5") (class "Default")
      (node (ref "J8") (pin "6") (pinfunction "6_6") (pintype "passive"))
      (node (ref "U3") (pin "49") (pinfunction "P3[5]/OA1+_49") (pintype "passive"))
    )
    (net (code "38") (name "/REED_ROW_6") (class "Default")
      (node (ref "J8") (pin "7") (pinfunction "7_7") (pintype "passive"))
      (node (ref "U3") (pin "51") (pinfunction "P3[6]/OA1OUT_51") (pintype "passive"))
    )
    (net (code "39") (name "/REED_ROW_7") (class "Default")
      (node (ref "J8") (pin "8") (pinfunction "8_8") (pintype "passive"))
      (node (ref "U3") (pin "52") (pinfunction "P3[7]/OA3OUT_52") (pintype "passive"))
    )
    (net (code "40") (name "/RX") (class "Default")
      (node (ref "J12") (pin "7") (pinfunction "7_7") (pintype "passive"))
      (node (ref "U3") (pin "28") (pinfunction "P1[7]_28") (pintype "passive"))
    )
    (net (code "41") (name "/SLP_1") (class "Default")
      (node (ref "J11") (pin "6") (pinfunction "6_6") (pintype "passive"))
      (node (ref "U3") (pin "89") (pinfunction "P6[0]_89") (pintype "passive"))
    )
    (net (code "42") (name "/SLP_2") (class "Default")
      (node (ref "J13") (pin "6") (pinfunction "6_6") (pintype "passive"))
      (node (ref "U3") (pin "92") (pinfunction "P6[3]_92") (pintype "passive"))
    )
    (net (code "43") (name "/STEP_1") (class "Default")
      (node (ref "J11") (pin "7") (pinfunction "7_7") (pintype "passive"))
      (node (ref "U3") (pin "90") (pinfunction "P6[1]_90") (pintype "passive"))
    )
    (net (code "44") (name "/STEP_2") (class "Default")
      (node (ref "J13") (pin "7") (pinfunction "7_7") (pintype "passive"))
      (node (ref "U3") (pin "6") (pinfunction "P6[4]_6") (pintype "passive"))
    )
    (net (code "45") (name "/SWDCK{slash}TCK") (class "Default")
      (node (ref "J12") (pin "2") (pinfunction "2_2") (pintype "passive"))
      (node (ref "U3") (pin "21") (pinfunction "P1[1]/SWDCK/TCK_21") (pintype "passive"))
    )
    (net (code "46") (name "/SWDIO{slash}TMS") (class "Default")
      (node (ref "J12") (pin "1") (pinfunction "1_1") (pintype "passive"))
      (node (ref "U3") (pin "20") (pinfunction "P1[0]/SWDIO/TMS_20") (pintype "passive"))
    )
    (net (code "47") (name "/SWV{slash}TDO") (class "Default")
      (node (ref "J12") (pin "3") (pinfunction "3_3") (pintype "passive"))
      (node (ref "U3") (pin "23") (pinfunction "P1[3]/SWV/TDO_23") (pintype "passive"))
    )
    (net (code "48") (name "/TDI") (class "Default")
      (node (ref "J12") (pin "4") (pinfunction "4_4") (pintype "passive"))
      (node (ref "U3") (pin "24") (pinfunction "P1[4]/TDI_24") (pintype "passive"))
    )
    (net (code "49") (name "/TX") (class "Default")
      (node (ref "J12") (pin "6") (pinfunction "6_6") (pintype "passive"))
      (node (ref "U3") (pin "27") (pinfunction "P1[6]_27") (pintype "passive"))
    )
    (net (code "50") (name "3.3V") (class "Default")
      (node (ref "C18") (pin "1") (pinfunction "1_1") (pintype "passive"))
      (node (ref "C2") (pin "2") (pinfunction "2_2") (pintype "passive"))
      (node (ref "C20") (pin "2") (pinfunction "2_2") (pintype "passive"))
      (node (ref "C21") (pin "2") (pinfunction "2_2") (pintype "passive"))
      (node (ref "C9") (pin "2") (pinfunction "2_2") (pintype "passive"))
      (node (ref "J6") (pin "1") (pinfunction "1_1") (pintype "passive"))
      (node (ref "R19") (pin "2") (pinfunction "2_2") (pintype "passive"))
      (node (ref "R20") (pin "1") (pinfunction "1_1") (pintype "passive"))
      (node (ref "R27") (pin "2") (pinfunction "2_2") (pintype "passive"))
      (node (ref "R29") (pin "1") (pinfunction "1_1") (pintype "passive"))
      (node (ref "R32") (pin "2") (pinfunction "2_2") (pintype "passive"))
      (node (ref "U1") (pin "2") (pinfunction "Vout_2") (pintype "passive"))
      (node (ref "U3") (pin "26") (pinfunction "VDDIO1_26") (pintype "passive"))
      (node (ref "U5") (pin "8") (pinfunction "VCC_8") (pintype "passive"))
    )
    (net (code "51") (name "5V") (class "Default")
      (node (ref "C10") (pin "2") (pinfunction "2_2") (pintype "passive"))
      (node (ref "C11") (pin "2") (pinfunction "2_2") (pintype "passive"))
      (node (ref "C15") (pin "2") (pinfunction "2_2") (pintype "passive"))
      (node (ref "C16") (pin "2") (pinfunction "2_2") (pintype "passive"))
      (node (ref "C3") (pin "2") (pinfunction "2_2") (pintype "passive"))
      (node (ref "C4") (pin "2") (pinfunction "2_2") (pintype "passive"))
      (node (ref "C5") (pin "2") (pinfunction "2_2") (pintype "passive"))
      (node (ref "C7") (pin "2") (pinfunction "2_2") (pintype "passive"))
      (node (ref "C8") (pin "2") (pinfunction "2_2") (pintype "passive"))
      (node (ref "J1") (pin "2") (pinfunction "2_2") (pintype "passive"))
      (node (ref "J11") (pin "10") (pinfunction "10_10") (pintype "passive"))
      (node (ref "J13") (pin "10") (pinfunction "10_10") (pintype "passive"))
      (node (ref "J6") (pin "2") (pinfunction "2_2") (pintype "passive"))
      (node (ref "R1") (pin "2") (pinfunction "2_2") (pintype "passive"))
      (node (ref "R2") (pin "2") (pinfunction "2_2") (pintype "passive"))
      (node (ref "R22") (pin "2") (pinfunction "2_2") (pintype "passive"))
      (node (ref "R24") (pin "2") (pinfunction "2_2") (pintype "passive"))
      (node (ref "R26") (pin "2") (pinfunction "2_2") (pintype "passive"))
      (node (ref "R3") (pin "2") (pinfunction "2_2") (pintype "passive"))
      (node (ref "R31") (pin "2") (pinfunction "2_2") (pintype "passive"))
      (node (ref "R34") (pin "2") (pinfunction "2_2") (pintype "passive"))
      (node (ref "R36") (pin "2") (pinfunction "2_2") (pintype "passive"))
      (node (ref "R38") (pin "2") (pinfunction "2_2") (pintype "passive"))
      (node (ref "R39") (pin "2") (pinfunction "2_2") (pintype "passive"))
      (node (ref "R4") (pin "2") (pinfunction "2_2") (pintype "passive"))
      (node (ref "R5") (pin "2") (pinfunction "2_2") (pintype "passive"))
      (node (ref "U2") (pin "2") (pinfunction "Vout_2") (pintype "passive"))
      (node (ref "U3") (pin "100") (pinfunction "VDDIO2_100") (pintype "passive"))
      (node (ref "U3") (pin "37") (pinfunction "VDDD_37") (pintype "passive"))
      (node (ref "U3") (pin "50") (pinfunction "VDDIO3_50") (pintype "passive"))
      (node (ref "U3") (pin "65") (pinfunction "VDDA_65") (pintype "passive"))
      (node (ref "U3") (pin "75") (pinfunction "VDDIO0_75") (pintype "passive"))
      (node (ref "U3") (pin "88") (pinfunction "VDDD_88") (pintype "passive"))
      (node (ref "VR1") (pin "1") (pinfunction "1_1") (pintype "passive"))
      (node (ref "VR2") (pin "1") (pinfunction "1_1") (pintype "passive"))
      (node (ref "VR2") (pin "2") (pinfunction "2_2") (pintype "passive"))
    )
    (net (code "52") (name "12V") (class "Default")
      (node (ref "C1") (pin "1") (pinfunction "1_1") (pintype "passive"))
      (node (ref "C13") (pin "1") (pinfunction "1_1") (pintype "passive"))
      (node (ref "C19") (pin "1") (pinfunction "1_1") (pintype "passive"))
      (node (ref "C22") (pin "1") (pinfunction "1_1") (pintype "passive"))
      (node (ref "C6") (pin "1") (pinfunction "1_1") (pintype "passive"))
      (node (ref "J11") (pin "12") (pinfunction "12_12") (pintype "passive"))
      (node (ref "J13") (pin "12") (pinfunction "12_12") (pintype "passive"))
      (node (ref "J3") (pin "1") (pinfunction "1_1") (pintype "passive"))
      (node (ref "U1") (pin "3") (pinfunction "Vin_3") (pintype "passive"))
      (node (ref "U2") (pin "3") (pinfunction "Vin_3") (pintype "passive"))
      (node (ref "U4") (pin "3") (pinfunction "Vin_3") (pintype "passive"))
    )
    (net (code "53") (name "GND") (class "Default")
      (node (ref "C1") (pin "2") (pinfunction "2_2") (pintype "passive"))
      (node (ref "C10") (pin "1") (pinfunction "1_1") (pintype "passive"))
      (node (ref "C11") (pin "1") (pinfunction "1_1") (pintype "passive"))
      (node (ref "C14") (pin "1") (pinfunction "1_1") (pintype "passive"))
      (node (ref "C15") (pin "1") (pinfunction "1_1") (pintype "passive"))
      (node (ref "C16") (pin "1") (pinfunction "1_1") (pintype "passive"))
      (node (ref "C17") (pin "1") (pinfunction "1_1") (pintype "passive"))
      (node (ref "C18") (pin "2") (pinfunction "2_2") (pintype "passive"))
      (node (ref "C19") (pin "2") (pinfunction "2_2") (pintype "passive"))
      (node (ref "C2") (pin "1") (pinfunction "1_1") (pintype "passive"))
      (node (ref "C20") (pin "1") (pinfunction "1_1") (pintype "passive"))
      (node (ref "C21") (pin "1") (pinfunction "1_1") (pintype "passive"))
      (node (ref "C22") (pin "2") (pinfunction "2_2") (pintype "passive"))
      (node (ref "C3") (pin "1") (pinfunction "1_1") (pintype "passive"))
      (node (ref "C4") (pin "1") (pinfunction "1_1") (pintype "passive"))
      (node (ref "C5") (pin "1") (pinfunction "1_1") (pintype "passive"))
      (node (ref "C6") (pin "2") (pinfunction "2_2") (pintype "passive"))
      (node (ref "C7") (pin "1") (pinfunction "1_1") (pintype "passive"))
      (node (ref "C8") (pin "1") (pinfunction "1_1") (pintype "passive"))
      (node (ref "C9") (pin "1") (pinfunction "1_1") (pintype "passive"))
      (node (ref "J1") (pin "1") (pinfunction "1_1") (pintype "passive"))
      (node (ref "J1") (pin "10") (pinfunction "10_10") (pintype "passive"))
      (node (ref "J1") (pin "16") (pinfunction "16_16") (pintype "passive"))
      (node (ref "J1") (pin "7") (pinfunction "7_7") (pintype "passive"))
      (node (ref "J1") (pin "8") (pinfunction "8_8") (pintype "passive"))
      (node (ref "J1") (pin "9") (pinfunction "9_9") (pintype "passive"))
      (node (ref "J11") (pin "1") (pinfunction "1_1") (pintype "passive"))
      (node (ref "J11") (pin "11") (pinfunction "11_11") (pintype "passive"))
      (node (ref "J11") (pin "9") (pinfunction "9_9") (pintype "passive"))
      (node (ref "J12") (pin "8") (pinfunction "8_8") (pintype "passive"))
      (node (ref "J13") (pin "1") (pinfunction "1_1") (pintype "passive"))
      (node (ref "J13") (pin "11") (pinfunction "11_11") (pintype "passive"))
      (node (ref "J13") (pin "9") (pinfunction "9_9") (pintype "passive"))
      (node (ref "J3") (pin "2") (pinfunction "2_2") (pintype "passive"))
      (node (ref "J4") (pin "5") (pinfunction "5_5") (pintype "passive"))
      (node (ref "J6") (pin "3") (pinfunction "3_3") (pintype "passive"))
      (node (ref "Q1") (pin "3") (pinfunction "D_3") (pintype "passive"))
      (node (ref "R10") (pin "1") (pinfunction "1_1") (pintype "passive"))
      (node (ref "R11") (pin "1") (pinfunction "1_1") (pintype "passive"))
      (node (ref "R12") (pin "1") (pinfunction "1_1") (pintype "passive"))
      (node (ref "R13") (pin "1") (pinfunction "1_1") (pintype "passive"))
      (node (ref "R14") (pin "1") (pinfunction "1_1") (pintype "passive"))
      (node (ref "R15") (pin "1") (pinfunction "1_1") (pintype "passive"))
      (node (ref "R16") (pin "1") (pinfunction "1_1") (pintype "passive"))
      (node (ref "R17") (pin "1") (pinfunction "1_1") (pintype "passive"))
      (node (ref "R18") (pin "1") (pinfunction "1_1") (pintype "passive"))
      (node (ref "R21") (pin "1") (pinfunction "1_1") (pintype "passive"))
      (node (ref "R23") (pin "1") (pinfunction "1_1") (pintype "passive"))
      (node (ref "R25") (pin "1") (pinfunction "1_1") (pintype "passive"))
      (node (ref "R30") (pin "1") (pinfunction "1_1") (pintype "passive"))
      (node (ref "R33") (pin "1") (pinfunction "1_1") (pintype "passive"))
      (node (ref "R35") (pin "1") (pinfunction "1_1") (pintype "passive"))
      (node (ref "R37") (pin "1") (pinfunction "1_1") (pintype "passive"))
      (node (ref "R7") (pin "1") (pinfunction "1_1") (pintype "passive"))
      (node (ref "R8") (pin "1") (pinfunction "1_1") (pintype "passive"))
      (node (ref "R9") (pin "1") (pinfunction "1_1") (pintype "passive"))
      (node (ref "S1") (pin "1") (pinfunction "1_1") (pintype "passive"))
      (node (ref "S2") (pin "2") (pinfunction "2_2") (pintype "passive"))
      (node (ref "S3") (pin "2") (pinfunction "2_2") (pintype "passive"))
      (node (ref "U1") (pin "1") (pinfunction "Gnd_1") (pintype "passive"))
      (node (ref "U2") (pin "1") (pinfunction "Gnd_1") (pintype "passive"))
      (node (ref "U3") (pin "10") (pinfunction "VSSB_10") (pintype "passive"))
      (node (ref "U3") (pin "12") (pinfunction "VBOOST_12") (pintype "passive"))
      (node (ref "U3") (pin "13") (pinfunction "VBAT_13") (pintype "passive"))
      (node (ref "U3") (pin "14") (pinfunction "VSSD_14") (pintype "passive"))
      (node (ref "U3") (pin "38") (pinfunction "VSSD_38") (pintype "passive"))
      (node (ref "U3") (pin "64") (pinfunction "VSSA_64") (pintype "passive"))
      (node (ref "U3") (pin "66") (pinfunction "VSSD_66") (pintype "passive"))
      (node (ref "U3") (pin "87") (pinfunction "VSSD_87") (pintype "passive"))
      (node (ref "U5") (pin "10") (pinfunction "GPIO15_10") (pintype "passive"))
      (node (ref "U5") (pin "13") (pinfunction "GPIO4_13") (pintype "passive"))
      (node (ref "U5") (pin "14") (pinfunction "GPIO5_14") (pintype "passive"))
      (node (ref "U5") (pin "2") (pinfunction "ADC_2") (pintype "passive"))
      (node (ref "U5") (pin "4") (pinfunction "GPIO16_4") (pintype "passive"))
      (node (ref "U5") (pin "5") (pinfunction "GPIO14_5") (pintype "passive"))
      (node (ref "U5") (pin "6") (pinfunction "GPIO12_6") (pintype "passive"))
      (node (ref "U5") (pin "7") (pinfunction "GPIO13_7") (pintype "passive"))
      (node (ref "U5") (pin "9") (pinfunction "GND_9") (pintype "passive"))
      (node (ref "VR1") (pin "3") (pinfunction "3_3") (pintype "passive"))
      (node (ref "VR3") (pin "2") (pinfunction "2_2") (pintype "passive"))
      (node (ref "VR3") (pin "3") (pinfunction "3_3") (pintype "passive"))
    )
    (net (code "54") (name "Net-(C14-Pad2)") (class "Default")
      (node (ref "C14") (pin "2") (pinfunction "2_2") (pintype "passive"))
      (node (ref "U3") (pin "39") (pinfunction "VCCD_39") (pintype "passive"))
      (node (ref "U3") (pin "86") (pinfunction "VCCD_86") (pintype "passive"))
    )
    (net (code "55") (name "Net-(J1-Pad3)") (class "Default")
      (node (ref "J1") (pin "3") (pinfunction "3_3") (pintype "passive"))
      (node (ref "VR1") (pin "2") (pinfunction "2_2") (pintype "passive"))
    )
    (net (code "56") (name "Net-(J1-Pad15)") (class "Default")
      (node (ref "J1") (pin "15") (pinfunction "15_15") (pintype "passive"))
      (node (ref "VR2") (pin "3") (pinfunction "3_3") (pintype "passive"))
    )
    (net (code "57") (name "Net-(J2-Pad1)") (class "Default")
      (node (ref "J2") (pin "1") (pinfunction "1_1") (pintype "passive"))
      (node (ref "R1") (pin "1") (pinfunction "1_1") (pintype "passive"))
    )
    (net (code "58") (name "Net-(J4-Pad1)") (class "Default")
      (node (ref "J4") (pin "1") (pinfunction "1_1") (pintype "passive"))
      (node (ref "R2") (pin "1") (pinfunction "1_1") (pintype "passive"))
    )
    (net (code "59") (name "Net-(J5-Pad1)") (class "Default")
      (node (ref "J5") (pin "1") (pinfunction "1_1") (pintype "passive"))
      (node (ref "R5") (pin "1") (pinfunction "1_1") (pintype "passive"))
    )
    (net (code "60") (name "Net-(J11-Pad2)") (class "Default")
      (node (ref "J11") (pin "2") (pinfunction "2_2") (pintype "passive"))
      (node (ref "R21") (pin "2") (pinfunction "2_2") (pintype "passive"))
      (node (ref "R22") (pin "1") (pinfunction "1_1") (pintype "passive"))
    )
    (net (code "61") (name "Net-(J11-Pad3)") (class "Default")
      (node (ref "J11") (pin "3") (pinfunction "3_3") (pintype "passive"))
      (node (ref "R23") (pin "2") (pinfunction "2_2") (pintype "passive"))
      (node (ref "R24") (pin "1") (pinfunction "1_1") (pintype "passive"))
    )
    (net (code "62") (name "Net-(J11-Pad4)") (class "Default")
      (node (ref "J11") (pin "4") (pinfunction "4_4") (pintype "passive"))
      (node (ref "R25") (pin "2") (pinfunction "2_2") (pintype "passive"))
      (node (ref "R26") (pin "1") (pinfunction "1_1") (pintype "passive"))
    )
    (net (code "63") (name "Net-(J11-Pad5)") (class "Default")
      (node (ref "J11") (pin "5") (pinfunction "5_5") (pintype "passive"))
      (node (ref "R31") (pin "1") (pinfunction "1_1") (pintype "passive"))
    )
    (net (code "64") (name "Net-(J13-Pad2)") (class "Default")
      (node (ref "J13") (pin "2") (pinfunction "2_2") (pintype "passive"))
      (node (ref "R33") (pin "2") (pinfunction "2_2") (pintype "passive"))
      (node (ref "R34") (pin "1") (pinfunction "1_1") (pintype "passive"))
    )
    (net (code "65") (name "Net-(J13-Pad3)") (class "Default")
      (node (ref "J13") (pin "3") (pinfunction "3_3") (pintype "passive"))
      (node (ref "R35") (pin "2") (pinfunction "2_2") (pintype "passive"))
      (node (ref "R36") (pin "1") (pinfunction "1_1") (pintype "passive"))
    )
    (net (code "66") (name "Net-(J13-Pad4)") (class "Default")
      (node (ref "J13") (pin "4") (pinfunction "4_4") (pintype "passive"))
      (node (ref "R37") (pin "2") (pinfunction "2_2") (pintype "passive"))
      (node (ref "R38") (pin "1") (pinfunction "1_1") (pintype "passive"))
    )
    (net (code "67") (name "Net-(J13-Pad5)") (class "Default")
      (node (ref "J13") (pin "5") (pinfunction "5_5") (pintype "passive"))
      (node (ref "R39") (pin "1") (pinfunction "1_1") (pintype "passive"))
    )
    (net (code "68") (name "Net-(Q1-G)") (class "Default")
      (node (ref "J10") (pin "2") (pinfunction "2_2") (pintype "passive"))
      (node (ref "Q1") (pin "1") (pinfunction "G_1") (pintype "passive"))
    )
    (net (code "69") (name "Net-(Q1-S)") (class "Default")
      (node (ref "Q1") (pin "2") (pinfunction "S_2") (pintype "passive"))
      (node (ref "R28") (pin "2") (pinfunction "2_2") (pintype "passive"))
      (node (ref "R30") (pin "2") (pinfunction "2_2") (pintype "passive"))
    )
    (net (code "70") (name "Net-(U3-VCCA)") (class "Default")
      (node (ref "C17") (pin "2") (pinfunction "2_2") (pintype "passive"))
      (node (ref "U3") (pin "63") (pinfunction "VCCA_63") (pintype "passive"))
    )
    (net (code "71") (name "Net-(U3-XRES)") (class "Default")
      (node (ref "R19") (pin "1") (pinfunction "1_1") (pintype "passive"))
      (node (ref "S1") (pin "2") (pinfunction "2_2") (pintype "passive"))
      (node (ref "U3") (pin "15") (pinfunction "XRES_15") (pintype "passive"))
    )
    (net (code "72") (name "Net-(U4-Gnd)") (class "Default")
      (node (ref "C12") (pin "1") (pinfunction "1_1") (pintype "passive"))
      (node (ref "C13") (pin "2") (pinfunction "2_2") (pintype "passive"))
      (node (ref "R6") (pin "1") (pinfunction "1_1") (pintype "passive"))
      (node (ref "U4") (pin "1") (pinfunction "Gnd_1") (pintype "passive"))
      (node (ref "VR3") (pin "1") (pinfunction "1_1") (pintype "passive"))
    )
    (net (code "73") (name "Net-(U5-CH_PD)") (class "Default")
      (node (ref "R27") (pin "1") (pinfunction "1_1") (pintype "passive"))
      (node (ref "U5") (pin "3") (pinfunction "CH_PD_3") (pintype "passive"))
    )
    (net (code "74") (name "Net-(U5-GPIO0)") (class "Default")
      (node (ref "R29") (pin "2") (pinfunction "2_2") (pintype "passive"))
      (node (ref "S3") (pin "1") (pinfunction "1_1") (pintype "passive"))
      (node (ref "U5") (pin "12") (pinfunction "GPIO0_12") (pintype "passive"))
    )
    (net (code "75") (name "Net-(U5-GPIO2)") (class "Default")
      (node (ref "R32") (pin "1") (pinfunction "1_1") (pintype "passive"))
      (node (ref "U5") (pin "11") (pinfunction "GPIO2_11") (pintype "passive"))
    )
    (net (code "76") (name "Vem") (class "Default")
      (node (ref "C12") (pin "2") (pinfunction "2_2") (pintype "passive"))
      (node (ref "J10") (pin "1") (pinfunction "1_1") (pintype "passive"))
      (node (ref "R6") (pin "2") (pinfunction "2_2") (pintype "passive"))
      (node (ref "U4") (pin "2") (pinfunction "Vout_2") (pintype "passive"))
    )
    (net (code "77") (name "unconnected-(U3-IND-Pad11)") (class "Default")
      (node (ref "U3") (pin "11") (pinfunction "IND_11") (pintype "passive+no_connect"))
    )
    (net (code "78") (name "unconnected-(U3-NC-Pad40)") (class "Default")
      (node (ref "U3") (pin "40") (pinfunction "NC_40") (pintype "passive+no_connect"))
    )
    (net (code "79") (name "unconnected-(U3-NC-Pad41)") (class "Default")
      (node (ref "U3") (pin "41") (pinfunction "NC_41") (pintype "passive+no_connect"))
    )
    (net (code "80") (name "unconnected-(U3-NC-Pad57)") (class "Default")
      (node (ref "U3") (pin "57") (pinfunction "NC_57") (pintype "passive+no_connect"))
    )
    (net (code "81") (name "unconnected-(U3-NC-Pad58)") (class "Default")
      (node (ref "U3") (pin "58") (pinfunction "NC_58") (pintype "passive+no_connect"))
    )
    (net (code "82") (name "unconnected-(U3-NC-Pad59)") (class "Default")
      (node (ref "U3") (pin "59") (pinfunction "NC_59") (pintype "passive+no_connect"))
    )
    (net (code "83") (name "unconnected-(U3-NC-Pad60)") (class "Default")
      (node (ref "U3") (pin "60") (pinfunction "NC_60") (pintype "passive+no_connect"))
    )
    (net (code "84") (name "unconnected-(U3-NC-Pad61)") (class "Default")
      (node (ref "U3") (pin "61") (pinfunction "NC_61") (pintype "passive+no_connect"))
    )
    (net (code "85") (name "unconnected-(U3-NC-Pad62)") (class "Default")
      (node (ref "U3") (pin "62") (pinfunction "NC_62") (pintype "passive+no_connect"))
    )
    (net (code "86") (name "unconnected-(U3-P1[2]-Pad22)") (class "Default")
      (node (ref "U3") (pin "22") (pinfunction "P1[2]_22") (pintype "passive+no_connect"))
    )
    (net (code "87") (name "unconnected-(U3-P2[7]-Pad3)") (class "Default")
      (node (ref "U3") (pin "3") (pinfunction "P2[7]_3") (pintype "passive+no_connect"))
    )
    (net (code "88") (name "unconnected-(U3-P4[4]-Pad82)") (class "Default")
      (node (ref "U3") (pin "82") (pinfunction "P4[4]_82") (pintype "passive+no_connect"))
    )
    (net (code "89") (name "unconnected-(U3-P4[5]-Pad83)") (class "Default")
      (node (ref "U3") (pin "83") (pinfunction "P4[5]_83") (pintype "passive+no_connect"))
    )
    (net (code "90") (name "unconnected-(U3-P4[6]-Pad84)") (class "Default")
      (node (ref "U3") (pin "84") (pinfunction "P4[6]_84") (pintype "passive+no_connect"))
    )
    (net (code "91") (name "unconnected-(U3-P4[7]-Pad85)") (class "Default")
      (node (ref "U3") (pin "85") (pinfunction "P4[7]_85") (pintype "passive+no_connect"))
    )
    (net (code "92") (name "unconnected-(U3-P5[3]-Pad19)") (class "Default")
      (node (ref "U3") (pin "19") (pinfunction "P5[3]_19") (pintype "passive+no_connect"))
    )
    (net (code "93") (name "unconnected-(U3-P5[4]-Pad31)") (class "Default")
      (node (ref "U3") (pin "31") (pinfunction "P5[4]_31") (pintype "passive+no_connect"))
    )
    (net (code "94") (name "unconnected-(U3-P5[5]-Pad32)") (class "Default")
      (node (ref "U3") (pin "32") (pinfunction "P5[5]_32") (pintype "passive+no_connect"))
    )
    (net (code "95") (name "unconnected-(U3-P5[6]-Pad33)") (class "Default")
      (node (ref "U3") (pin "33") (pinfunction "P5[6]_33") (pintype "passive+no_connect"))
    )
    (net (code "96") (name "unconnected-(U3-P5[7]-Pad34)") (class "Default")
      (node (ref "U3") (pin "34") (pinfunction "P5[7]_34") (pintype "passive+no_connect"))
    )
    (net (code "97") (name "unconnected-(U3-P12[4]{slash}SIO-Pad4)") (class "Default")
      (node (ref "U3") (pin "4") (pinfunction "P12[4]/SIO_4") (pintype "passive+no_connect"))
    )
    (net (code "98") (name "unconnected-(U3-P12[5]{slash}SIO-Pad5)") (class "Default")
      (node (ref "U3") (pin "5") (pinfunction "P12[5]/SIO_5") (pintype "passive+no_connect"))
    )
    (net (code "99") (name "unconnected-(U3-P12[6]{slash}SIO-Pad29)") (class "Default")
      (node (ref "U3") (pin "29") (pinfunction "P12[6]/SIO_29") (pintype "passive+no_connect"))
    )
    (net (code "100") (name "unconnected-(U3-P12[7]{slash}SIO-Pad30)") (class "Default")
      (node (ref "U3") (pin "30") (pinfunction "P12[7]/SIO_30") (pintype "passive+no_connect"))
    )
    (net (code "101") (name "unconnected-(U3-P15[0]{slash}MHZXOUT-Pad42)") (class "Default")
      (node (ref "U3") (pin "42") (pinfunction "P15[0]/MHZXOUT_42") (pintype "passive+no_connect"))
    )
    (net (code "102") (name "unconnected-(U3-P15[1]{slash}MHZXIN-Pad43)") (class "Default")
      (node (ref "U3") (pin "43") (pinfunction "P15[1]/MHZXIN_43") (pintype "passive+no_connect"))
    )
    (net (code "103") (name "unconnected-(U3-P15[2]{slash}KHZXOUT-Pad55)") (class "Default")
      (node (ref "U3") (pin "55") (pinfunction "P15[2]/KHZXOUT_55") (pintype "passive+no_connect"))
    )
    (net (code "104") (name "unconnected-(U3-P15[3]{slash}KHZXIN-Pad56)") (class "Default")
      (node (ref "U3") (pin "56") (pinfunction "P15[3]/KHZXIN_56") (pintype "passive+no_connect"))
    )
    (net (code "105") (name "unconnected-(U3-P15[4]-Pad93)") (class "Default")
      (node (ref "U3") (pin "93") (pinfunction "P15[4]_93") (pintype "passive+no_connect"))
    )
    (net (code "106") (name "unconnected-(U3-P15[5]-Pad94)") (class "Default")
      (node (ref "U3") (pin "94") (pinfunction "P15[5]_94") (pintype "passive+no_connect"))
    )
    (net (code "107") (name "unconnected-(U3-P15[6]{slash}USBD+-Pad35)") (class "Default")
      (node (ref "U3") (pin "35") (pinfunction "P15[6]/USBD+_35") (pintype "passive+no_connect"))
    )
    (net (code "108") (name "unconnected-(U3-P15[7]{slash}USBD--Pad36)") (class "Default")
      (node (ref "U3") (pin "36") (pinfunction "P15[7]/USBD-_36") (pintype "passive+no_connect"))
    )
  )
)
